# TestBench_SD_Shield.net
KiCad netlist of a schematic drawn in EAGLE
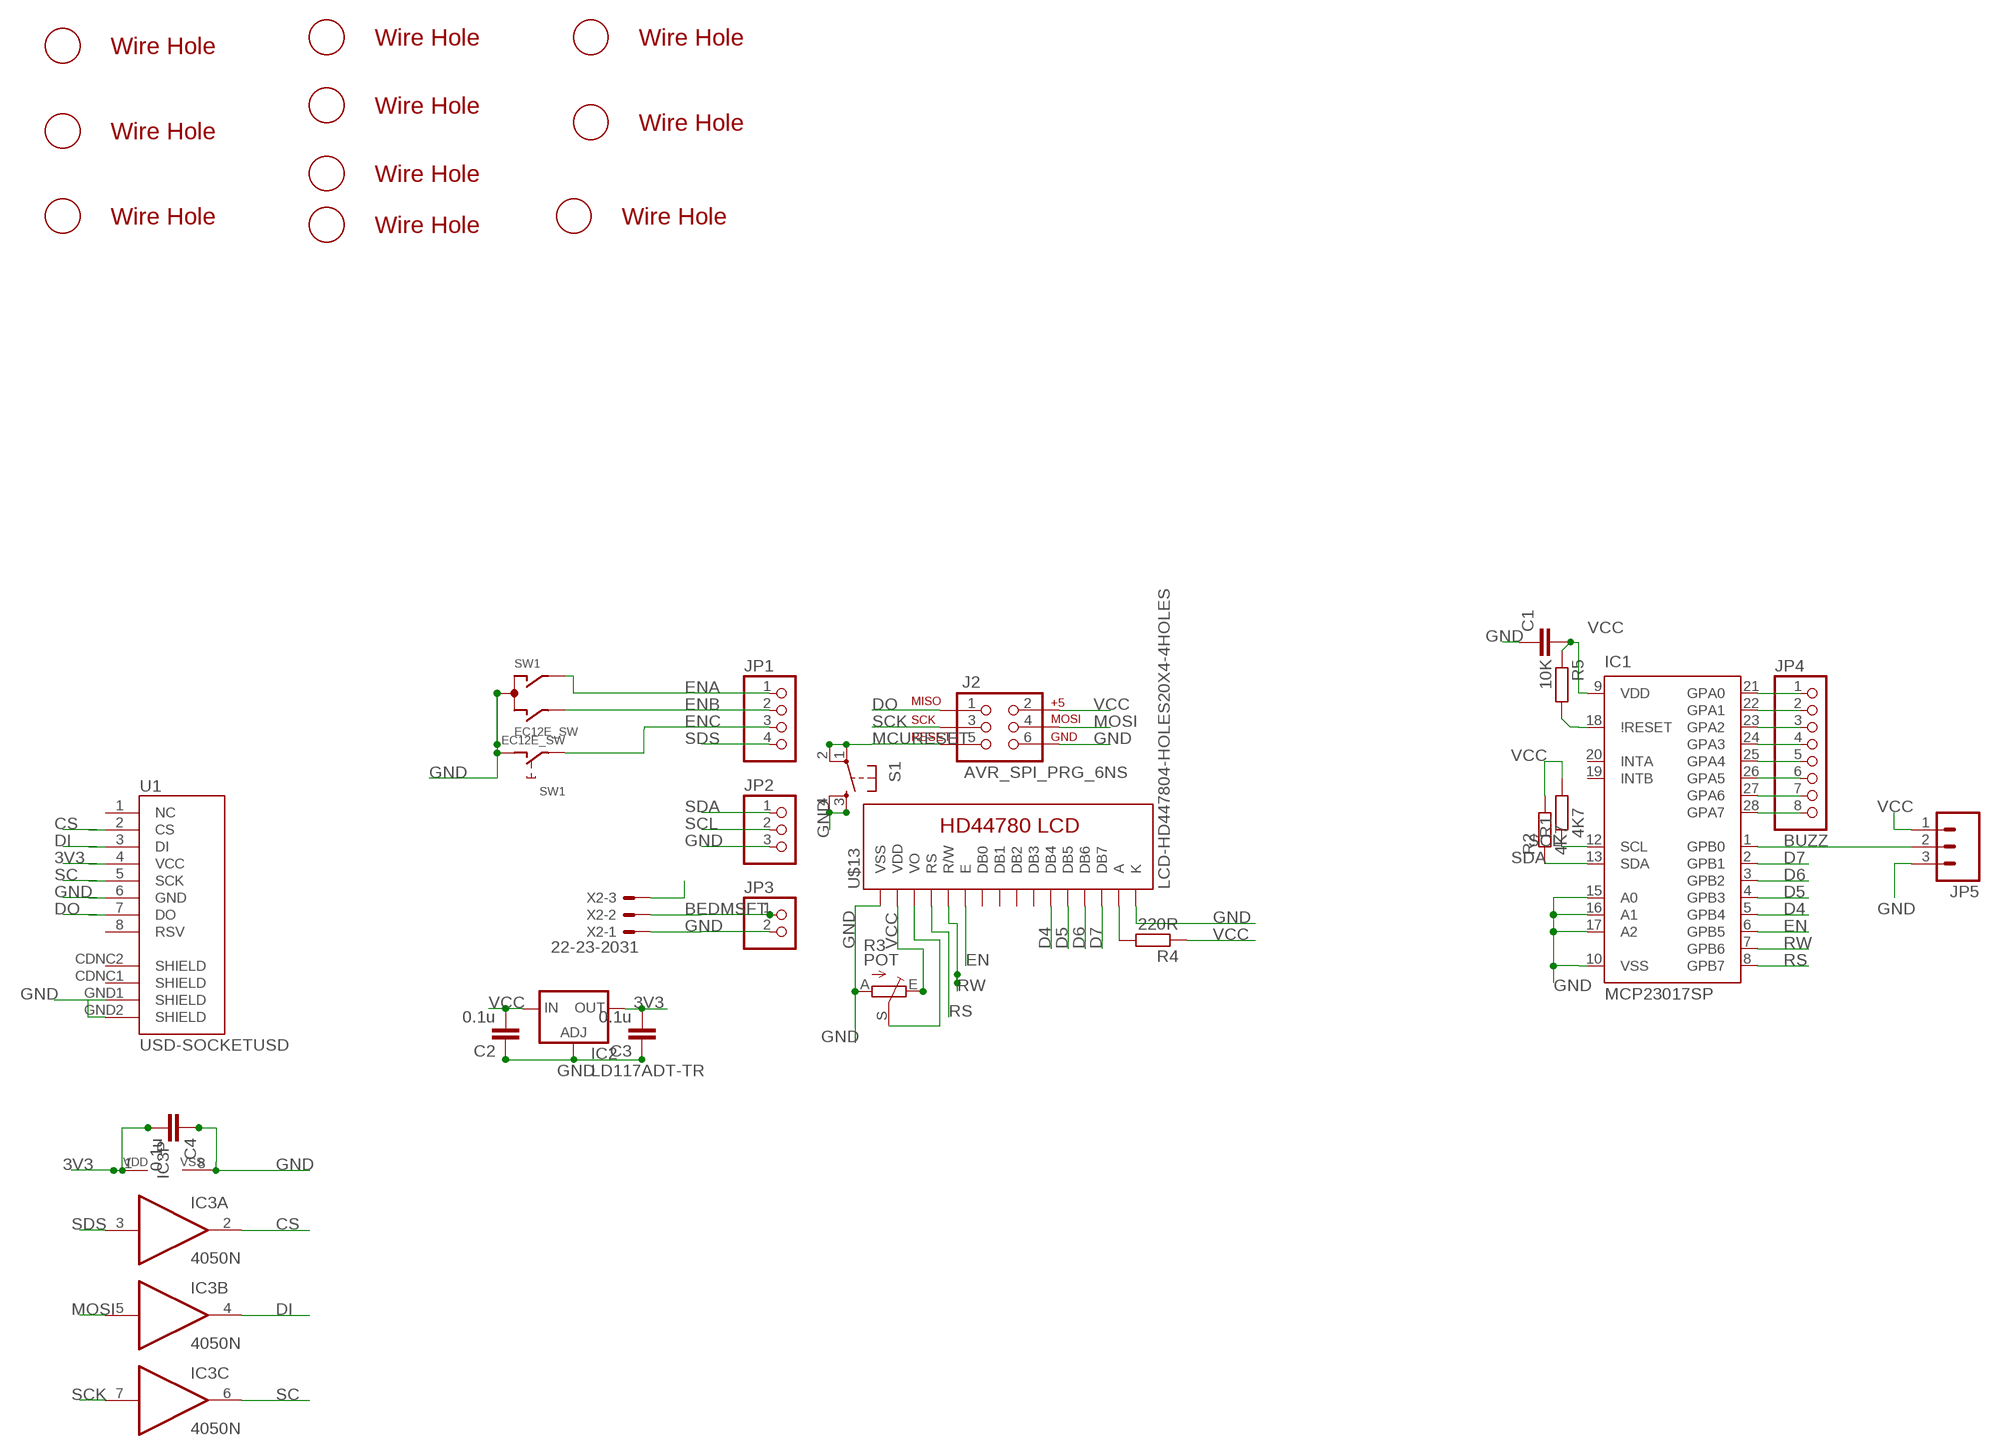
[diagram p0: schematic, sheet 1]

(export (version "E")
  (design (tool "Eeschema 10.0.6"))
  (components
    (comp (ref "C1")
      (value "CAPKIT")
      (footprint "eagle-import:CAP-PTH-SMALL-KIT")
      (libsource (lib "eagle-import") (part "CAPKIT"))
    )
    (comp (ref "C2")
      (value "0.1u")
      (footprint "eagle-import:CAP-PTH-SMALL-KIT")
      (libsource (lib "eagle-import") (part "CAPKIT"))
    )
    (comp (ref "C3")
      (value "0.1u")
      (footprint "eagle-import:CAP-PTH-SMALL-KIT")
      (libsource (lib "eagle-import") (part "CAPKIT"))
    )
    (comp (ref "C4")
      (value "0.1u")
      (footprint "eagle-import:CAP-PTH-SMALL-KIT")
      (libsource (lib "eagle-import") (part "CAPKIT"))
    )
    (comp (ref "IC1")
      (value "MCP23017SP")
      (footprint "eagle-import:DIL28-3")
      (libsource (lib "eagle-import") (part "MCP23017SP"))
    )
    (comp (ref "IC2")
      (value "LD117ADT-TR")
      (footprint "eagle-import:DPACK")
      (libsource (lib "eagle-import") (part "LD117A?DT-TR"))
    )
    (comp (ref "IC3")
      (value "4050N")
      (footprint "eagle-import:DIL16")
      (libsource (lib "eagle-import") (part "4050N"))
    )
    (comp (ref "J2")
      (value "AVR_SPI_PRG_6NS")
      (footprint "eagle-import:2X3-NS")
      (libsource (lib "eagle-import") (part "AVR_SPI_PRG_6NS"))
    )
    (comp (ref "JP1")
      (value "PINHD-1X4")
      (footprint "eagle-import:1X04")
      (libsource (lib "eagle-import") (part "PINHD-1X4"))
    )
    (comp (ref "JP2")
      (value "PINHD-1X3")
      (footprint "eagle-import:1X03")
      (libsource (lib "eagle-import") (part "PINHD-1X3"))
    )
    (comp (ref "JP3")
      (value "PINHD-1X2")
      (footprint "eagle-import:1X02")
      (libsource (lib "eagle-import") (part "PINHD-1X2"))
    )
    (comp (ref "JP4")
      (value "PINHD-1X8")
      (footprint "eagle-import:1X08")
      (libsource (lib "eagle-import") (part "PINHD-1X8"))
    )
    (comp (ref "JP5")
      (value "M03LONGPADS")
      (footprint "eagle-import:1X03_LONGPADS")
      (libsource (lib "eagle-import") (part "M03LONGPADS"))
    )
    (comp (ref "R1")
      (value "4K7")
      (footprint "eagle-import:0204_7")
      (libsource (lib "eagle-import") (part "R-EU_0204/7"))
    )
    (comp (ref "R2")
      (value "4K7")
      (footprint "eagle-import:0204_7")
      (libsource (lib "eagle-import") (part "R-EU_0204/7"))
    )
    (comp (ref "R3")
      (value "POT")
      (footprint "eagle-import:CA9V")
      (libsource (lib "eagle-import") (part "TRIM_EU-CA9V"))
    )
    (comp (ref "R4")
      (value "220R")
      (footprint "eagle-import:0204_7")
      (libsource (lib "eagle-import") (part "R-EU_0204/7"))
    )
    (comp (ref "R5")
      (value "10K")
      (footprint "eagle-import:0204_7")
      (libsource (lib "eagle-import") (part "R-EU_0204/7"))
    )
    (comp (ref "S1")
      (value "TAC_SWITCHPTH")
      (footprint "eagle-import:TACTILE-PTH")
      (libsource (lib "eagle-import") (part "TAC_SWITCHPTH"))
    )
    (comp (ref "SW1")
      (value "EC12E_SW")
      (footprint "eagle-import:ALPS_EC12E_SW")
      (fields (field (name "MPN") "EC12E2424407"))
      (libsource (lib "eagle-import") (part "EC12E_SW"))
    )
    (comp (ref "U$1")
      (value "3MMHOLE")
      (footprint "eagle-import:3MMHOLE")
      (libsource (lib "eagle-import") (part "3MMHOLE"))
    )
    (comp (ref "U$3")
      (value "3MMHOLE")
      (footprint "eagle-import:3MMHOLE")
      (libsource (lib "eagle-import") (part "3MMHOLE"))
    )
    (comp (ref "U$5")
      (value "3MMHOLE")
      (footprint "eagle-import:3MMHOLE")
      (libsource (lib "eagle-import") (part "3MMHOLE"))
    )
    (comp (ref "U$6")
      (value "3MMHOLE")
      (footprint "eagle-import:3MMHOLE")
      (libsource (lib "eagle-import") (part "3MMHOLE"))
    )
    (comp (ref "U$7")
      (value "3MMHOLE")
      (footprint "eagle-import:3MMHOLE")
      (libsource (lib "eagle-import") (part "3MMHOLE"))
    )
    (comp (ref "U$8")
      (value "3MMHOLE")
      (footprint "eagle-import:3MMHOLE")
      (libsource (lib "eagle-import") (part "3MMHOLE"))
    )
    (comp (ref "U$9")
      (value "3MMHOLE")
      (footprint "eagle-import:3MMHOLE")
      (libsource (lib "eagle-import") (part "3MMHOLE"))
    )
    (comp (ref "U$10")
      (value "3MMHOLE")
      (footprint "eagle-import:3MMHOLE")
      (libsource (lib "eagle-import") (part "3MMHOLE"))
    )
    (comp (ref "U$11")
      (value "3MMHOLE")
      (footprint "eagle-import:3MMHOLE")
      (libsource (lib "eagle-import") (part "3MMHOLE"))
    )
    (comp (ref "U$12")
      (value "3MMHOLE")
      (footprint "eagle-import:3MMHOLE")
      (libsource (lib "eagle-import") (part "3MMHOLE"))
    )
    (comp (ref "U$13")
      (value "LCD-HD447804-HOLES20X4-4HOLES")
      (footprint "eagle-import:LCD-20X4-4HOLES")
      (libsource (lib "eagle-import") (part "LCD-HD4478020X4-4HOLES4-HOLES"))
    )
    (comp (ref "U1")
      (value "USD-SOCKETUSD")
      (footprint "eagle-import:USD-SOCKET-PP")
      (libsource (lib "eagle-import") (part "USD-SOCKETUSD"))
    )
    (comp (ref "X2")
      (value "22-23-2031")
      (footprint "eagle-import:22-23-2031")
      (fields (field (name "MF") "MOLEX"))
      (libsource (lib "eagle-import") (part "22-23-2031"))
    )
  )
  (nets
    (net (code "1") (name "/3V3") (class "Default")
      (node (ref "C3") (pin "2") (pinfunction "2_2") (pintype "passive"))
      (node (ref "C4") (pin "2") (pinfunction "2_2") (pintype "passive"))
      (node (ref "IC2") (pin "4") (pinfunction "OUT_4") (pintype "passive"))
      (node (ref "IC3") (pin "1") (pinfunction "VDD_1") (pintype "power_in"))
      (node (ref "U1") (pin "4") (pinfunction "VCC_4") (pintype "bidirectional"))
    )
    (net (code "2") (name "/BEDMSFT") (class "Default")
      (node (ref "JP3") (pin "1") (pinfunction "1_1") (pintype "passive"))
      (node (ref "X2") (pin "2") (pinfunction "S_2") (pintype "passive"))
    )
    (net (code "3") (name "/BUZZ") (class "Default")
      (node (ref "IC1") (pin "1") (pinfunction "GPB0_1") (pintype "bidirectional"))
      (node (ref "JP5") (pin "2") (pinfunction "2_2") (pintype "passive"))
    )
    (net (code "4") (name "/CS") (class "Default")
      (node (ref "IC3") (pin "2") (pinfunction "O_2") (pintype "output"))
      (node (ref "U1") (pin "2") (pinfunction "CS_2") (pintype "bidirectional"))
    )
    (net (code "5") (name "/D4") (class "Default")
      (node (ref "IC1") (pin "5") (pinfunction "GPB4_5") (pintype "bidirectional"))
      (node (ref "U$13") (pin "P$11") (pinfunction "DB4_P$11") (pintype "bidirectional"))
    )
    (net (code "6") (name "/D5") (class "Default")
      (node (ref "IC1") (pin "4") (pinfunction "GPB3_4") (pintype "bidirectional"))
      (node (ref "U$13") (pin "P$12") (pinfunction "DB5_P$12") (pintype "bidirectional"))
    )
    (net (code "7") (name "/D6") (class "Default")
      (node (ref "IC1") (pin "3") (pinfunction "GPB2_3") (pintype "bidirectional"))
      (node (ref "U$13") (pin "P$13") (pinfunction "DB6_P$13") (pintype "bidirectional"))
    )
    (net (code "8") (name "/D7") (class "Default")
      (node (ref "IC1") (pin "2") (pinfunction "GPB1_2") (pintype "bidirectional"))
      (node (ref "U$13") (pin "P$14") (pinfunction "DB7_P$14") (pintype "bidirectional"))
    )
    (net (code "9") (name "/DI") (class "Default")
      (node (ref "IC3") (pin "4") (pinfunction "O_4") (pintype "output"))
      (node (ref "U1") (pin "3") (pinfunction "DI_3") (pintype "bidirectional"))
    )
    (net (code "10") (name "/DO") (class "Default")
      (node (ref "J2") (pin "1") (pinfunction "1_1") (pintype "passive"))
      (node (ref "U1") (pin "7") (pinfunction "DO_7") (pintype "bidirectional"))
    )
    (net (code "11") (name "/EN") (class "Default")
      (node (ref "IC1") (pin "6") (pinfunction "GPB5_6") (pintype "bidirectional"))
      (node (ref "U$13") (pin "P$6") (pinfunction "E_P$6") (pintype "input"))
    )
    (net (code "12") (name "/ENA") (class "Default")
      (node (ref "JP1") (pin "1") (pinfunction "1_1") (pintype "passive"))
      (node (ref "SW1") (pin "A") (pinfunction "A_A") (pintype "passive"))
    )
    (net (code "13") (name "/ENB") (class "Default")
      (node (ref "JP1") (pin "2") (pinfunction "2_2") (pintype "passive"))
      (node (ref "SW1") (pin "B") (pinfunction "B_B") (pintype "passive"))
    )
    (net (code "14") (name "/ENC") (class "Default")
      (node (ref "JP1") (pin "3") (pinfunction "3_3") (pintype "passive"))
      (node (ref "SW1") (pin "E") (pinfunction "2_E") (pintype "passive"))
    )
    (net (code "15") (name "/GND") (class "Default")
      (node (ref "C1") (pin "1") (pinfunction "1_1") (pintype "passive"))
      (node (ref "C2") (pin "1") (pinfunction "1_1") (pintype "passive"))
      (node (ref "C3") (pin "1") (pinfunction "1_1") (pintype "passive"))
      (node (ref "C4") (pin "1") (pinfunction "1_1") (pintype "passive"))
      (node (ref "IC1") (pin "10") (pinfunction "VSS_10") (pintype "power_in"))
      (node (ref "IC1") (pin "15") (pinfunction "A0_15") (pintype "input"))
      (node (ref "IC1") (pin "16") (pinfunction "A1_16") (pintype "input"))
      (node (ref "IC1") (pin "17") (pinfunction "A2_17") (pintype "input"))
      (node (ref "IC2") (pin "1") (pinfunction "ADJ_1") (pintype "input"))
      (node (ref "IC3") (pin "8") (pinfunction "VSS_8") (pintype "power_in"))
      (node (ref "J2") (pin "6") (pinfunction "6_6") (pintype "passive"))
      (node (ref "JP2") (pin "3") (pinfunction "3_3") (pintype "passive"))
      (node (ref "JP3") (pin "2") (pinfunction "2_2") (pintype "passive"))
      (node (ref "JP5") (pin "3") (pinfunction "3_3") (pintype "passive"))
      (node (ref "R3") (pin "A") (pinfunction "A_A") (pintype "passive"))
      (node (ref "S1") (pin "3") (pinfunction "3_3") (pintype "passive"))
      (node (ref "S1") (pin "4") (pinfunction "4_4") (pintype "passive"))
      (node (ref "SW1") (pin "C") (pinfunction "C_C") (pintype "passive"))
      (node (ref "SW1") (pin "D") (pinfunction "1_D") (pintype "passive"))
      (node (ref "U$13") (pin "P$1") (pinfunction "VSS_P$1") (pintype "power_in"))
      (node (ref "U$13") (pin "P$16") (pinfunction "K_P$16") (pintype "power_in"))
      (node (ref "U1") (pin "6") (pinfunction "GND_6") (pintype "bidirectional"))
      (node (ref "U1") (pin "GND1") (pinfunction "SHIELD_GND1") (pintype "bidirectional"))
      (node (ref "U1") (pin "GND2") (pinfunction "SHIELD_GND2") (pintype "bidirectional"))
      (node (ref "X2") (pin "1") (pinfunction "S_1") (pintype "passive"))
    )
    (net (code "16") (name "/MCURESET") (class "Default")
      (node (ref "J2") (pin "5") (pinfunction "5_5") (pintype "passive"))
      (node (ref "S1") (pin "1") (pinfunction "1_1") (pintype "passive"))
      (node (ref "S1") (pin "2") (pinfunction "2_2") (pintype "passive"))
    )
    (net (code "17") (name "/MOSI") (class "Default")
      (node (ref "IC3") (pin "5") (pinfunction "I_5") (pintype "input"))
      (node (ref "J2") (pin "4") (pinfunction "4_4") (pintype "passive"))
    )
    (net (code "18") (name "/RS") (class "Default")
      (node (ref "IC1") (pin "8") (pinfunction "GPB7_8") (pintype "bidirectional"))
      (node (ref "U$13") (pin "P$4") (pinfunction "RS_P$4") (pintype "input"))
    )
    (net (code "19") (name "/RW") (class "Default")
      (node (ref "IC1") (pin "7") (pinfunction "GPB6_7") (pintype "bidirectional"))
      (node (ref "U$13") (pin "P$5") (pinfunction "R/W_P$5") (pintype "input"))
    )
    (net (code "20") (name "/SC") (class "Default")
      (node (ref "IC3") (pin "6") (pinfunction "O_6") (pintype "output"))
      (node (ref "U1") (pin "5") (pinfunction "SCK_5") (pintype "bidirectional"))
    )
    (net (code "21") (name "/SCK") (class "Default")
      (node (ref "IC3") (pin "7") (pinfunction "I_7") (pintype "input"))
      (node (ref "J2") (pin "3") (pinfunction "3_3") (pintype "passive"))
    )
    (net (code "22") (name "/SCL") (class "Default")
      (node (ref "IC1") (pin "12") (pinfunction "SCL_12") (pintype "input"))
      (node (ref "JP2") (pin "2") (pinfunction "2_2") (pintype "passive"))
      (node (ref "R1") (pin "1") (pinfunction "1_1") (pintype "passive"))
    )
    (net (code "23") (name "/SDA") (class "Default")
      (node (ref "IC1") (pin "13") (pinfunction "SDA_13") (pintype "bidirectional"))
      (node (ref "JP2") (pin "1") (pinfunction "1_1") (pintype "passive"))
      (node (ref "R2") (pin "1") (pinfunction "1_1") (pintype "passive"))
    )
    (net (code "24") (name "/SDS") (class "Default")
      (node (ref "IC3") (pin "3") (pinfunction "I_3") (pintype "input"))
      (node (ref "JP1") (pin "4") (pinfunction "4_4") (pintype "passive"))
    )
    (net (code "25") (name "/VCC") (class "Default")
      (node (ref "C1") (pin "2") (pinfunction "2_2") (pintype "passive"))
      (node (ref "C2") (pin "2") (pinfunction "2_2") (pintype "passive"))
      (node (ref "IC1") (pin "9") (pinfunction "VDD_9") (pintype "power_in"))
      (node (ref "IC2") (pin "3") (pinfunction "IN_3") (pintype "input"))
      (node (ref "J2") (pin "2") (pinfunction "2_2") (pintype "passive"))
      (node (ref "JP5") (pin "1") (pinfunction "1_1") (pintype "passive"))
      (node (ref "R1") (pin "2") (pinfunction "2_2") (pintype "passive"))
      (node (ref "R2") (pin "2") (pinfunction "2_2") (pintype "passive"))
      (node (ref "R3") (pin "E") (pinfunction "E_E") (pintype "passive"))
      (node (ref "R4") (pin "1") (pinfunction "1_1") (pintype "passive"))
      (node (ref "R5") (pin "1") (pinfunction "1_1") (pintype "passive"))
      (node (ref "U$13") (pin "P$2") (pinfunction "VDD_P$2") (pintype "power_in"))
    )
    (net (code "26") (name "Net-(IC1-GPA0)") (class "Default")
      (node (ref "IC1") (pin "21") (pinfunction "GPA0_21") (pintype "bidirectional"))
      (node (ref "JP4") (pin "1") (pinfunction "1_1") (pintype "passive"))
    )
    (net (code "27") (name "Net-(IC1-GPA1)") (class "Default")
      (node (ref "IC1") (pin "22") (pinfunction "GPA1_22") (pintype "bidirectional"))
      (node (ref "JP4") (pin "2") (pinfunction "2_2") (pintype "passive"))
    )
    (net (code "28") (name "Net-(IC1-GPA2)") (class "Default")
      (node (ref "IC1") (pin "23") (pinfunction "GPA2_23") (pintype "bidirectional"))
      (node (ref "JP4") (pin "3") (pinfunction "3_3") (pintype "passive"))
    )
    (net (code "29") (name "Net-(IC1-GPA3)") (class "Default")
      (node (ref "IC1") (pin "24") (pinfunction "GPA3_24") (pintype "bidirectional"))
      (node (ref "JP4") (pin "4") (pinfunction "4_4") (pintype "passive"))
    )
    (net (code "30") (name "Net-(IC1-GPA4)") (class "Default")
      (node (ref "IC1") (pin "25") (pinfunction "GPA4_25") (pintype "bidirectional"))
      (node (ref "JP4") (pin "5") (pinfunction "5_5") (pintype "passive"))
    )
    (net (code "31") (name "Net-(IC1-GPA5)") (class "Default")
      (node (ref "IC1") (pin "26") (pinfunction "GPA5_26") (pintype "bidirectional"))
      (node (ref "JP4") (pin "6") (pinfunction "6_6") (pintype "passive"))
    )
    (net (code "32") (name "Net-(IC1-GPA6)") (class "Default")
      (node (ref "IC1") (pin "27") (pinfunction "GPA6_27") (pintype "bidirectional"))
      (node (ref "JP4") (pin "7") (pinfunction "7_7") (pintype "passive"))
    )
    (net (code "33") (name "Net-(IC1-GPA7)") (class "Default")
      (node (ref "IC1") (pin "28") (pinfunction "GPA7_28") (pintype "bidirectional"))
      (node (ref "JP4") (pin "8") (pinfunction "8_8") (pintype "passive"))
    )
    (net (code "34") (name "Net-(IC1-\\~{RESET})") (class "Default")
      (node (ref "IC1") (pin "18") (pinfunction "\\~{RESET}_18") (pintype "input"))
      (node (ref "R5") (pin "2") (pinfunction "2_2") (pintype "passive"))
    )
    (net (code "35") (name "Net-(U$13-A)") (class "Default")
      (node (ref "R4") (pin "2") (pinfunction "2_2") (pintype "passive"))
      (node (ref "U$13") (pin "P$15") (pinfunction "A_P$15") (pintype "power_in"))
    )
    (net (code "36") (name "Net-(U$13-VO)") (class "Default")
      (node (ref "R3") (pin "S") (pinfunction "S_S") (pintype "passive"))
      (node (ref "U$13") (pin "P$3") (pinfunction "VO_P$3") (pintype "bidirectional"))
    )
    (net (code "37") (name "unconnected-(IC1-INTA-Pad20)") (class "Default")
      (node (ref "IC1") (pin "20") (pinfunction "INTA_20") (pintype "output"))
    )
    (net (code "38") (name "unconnected-(IC1-INTB-Pad19)") (class "Default")
      (node (ref "IC1") (pin "19") (pinfunction "INTB_19") (pintype "output"))
    )
    (net (code "39") (name "unconnected-(U$13-DB0-PadP$7)") (class "Default")
      (node (ref "U$13") (pin "P$7") (pinfunction "DB0_P$7") (pintype "bidirectional"))
    )
    (net (code "40") (name "unconnected-(U$13-DB1-PadP$8)") (class "Default")
      (node (ref "U$13") (pin "P$8") (pinfunction "DB1_P$8") (pintype "bidirectional"))
    )
    (net (code "41") (name "unconnected-(U$13-DB2-PadP$9)") (class "Default")
      (node (ref "U$13") (pin "P$9") (pinfunction "DB2_P$9") (pintype "bidirectional"))
    )
    (net (code "42") (name "unconnected-(U$13-DB3-PadP$10)") (class "Default")
      (node (ref "U$13") (pin "P$10") (pinfunction "DB3_P$10") (pintype "bidirectional"))
    )
    (net (code "43") (name "unconnected-(U1-NC-Pad1)") (class "Default")
      (node (ref "U1") (pin "1") (pinfunction "NC_1") (pintype "bidirectional"))
    )
    (net (code "44") (name "unconnected-(U1-RSV-Pad8)") (class "Default")
      (node (ref "U1") (pin "8") (pinfunction "RSV_8") (pintype "bidirectional"))
    )
    (net (code "45") (name "unconnected-(U1-SHIELD-PadCDNC1)") (class "Default")
      (node (ref "U1") (pin "CDNC1") (pinfunction "SHIELD_CDNC1") (pintype "bidirectional"))
    )
    (net (code "46") (name "unconnected-(U1-SHIELD-PadCDNC2)") (class "Default")
      (node (ref "U1") (pin "CDNC2") (pinfunction "SHIELD_CDNC2") (pintype "bidirectional"))
    )
    (net (code "47") (name "unconnected-(X2C-S-Pad3)") (class "Default")
      (node (ref "X2") (pin "3") (pinfunction "S_3") (pintype "passive"))
    )
  )
)
